# testing.net
KiCad netlist of a schematic drawn in EAGLE
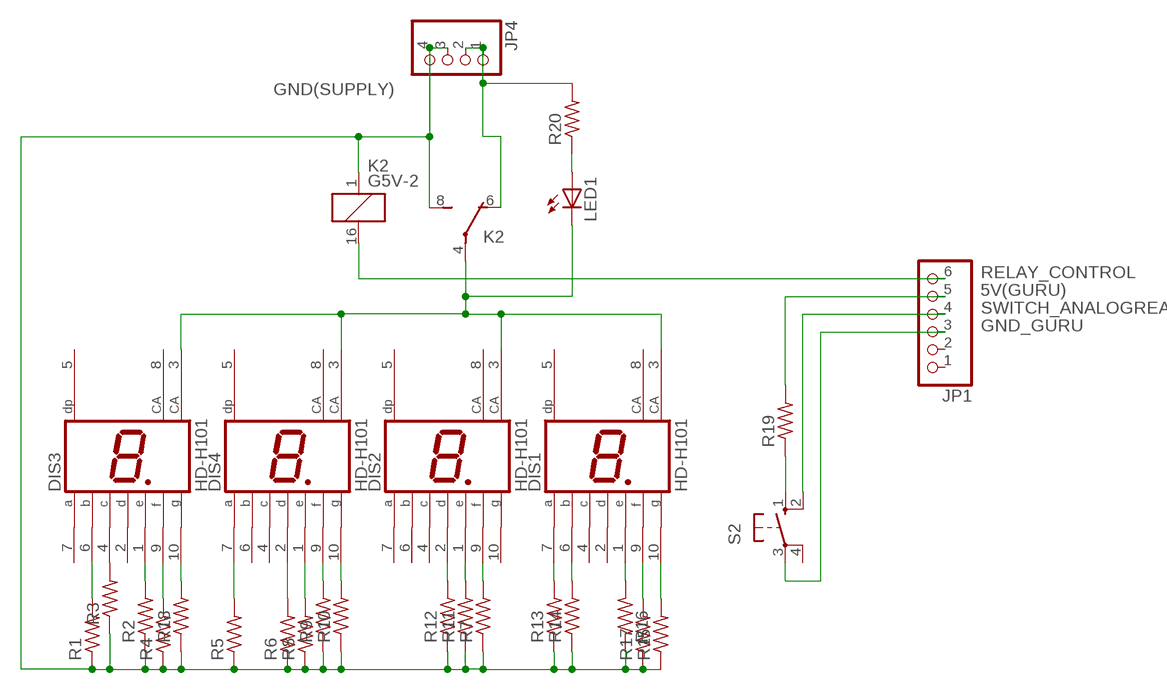
[diagram p0: schematic, sheet 1]

(export (version "E")
  (design (tool "Eeschema 10.0.6"))
  (components
    (comp (ref "DIS1")
      (value "HD-H101")
      (footprint "eagle-import:HDSP-M")
      (libsource (lib "eagle-import") (part "HD-H101"))
    )
    (comp (ref "DIS2")
      (value "HD-H101")
      (footprint "eagle-import:HDSP-M")
      (libsource (lib "eagle-import") (part "HD-H101"))
    )
    (comp (ref "DIS3")
      (value "HD-H101")
      (footprint "eagle-import:HDSP-M")
      (libsource (lib "eagle-import") (part "HD-H101"))
    )
    (comp (ref "DIS4")
      (value "HD-H101")
      (footprint "eagle-import:HDSP-M")
      (libsource (lib "eagle-import") (part "HD-H101"))
    )
    (comp (ref "JP1")
      (value "PINHD-1X6/90")
      (footprint "eagle-import:1X06_90")
      (libsource (lib "eagle-import") (part "PINHD-1X6/90"))
    )
    (comp (ref "JP4")
      (value "PINHD-1X4")
      (footprint "eagle-import:1X04")
      (libsource (lib "eagle-import") (part "PINHD-1X4"))
    )
    (comp (ref "K2")
      (value "G5V-2")
      (footprint "eagle-import:G5V-2")
      (fields (field (name "MPN") "G5V-2 5DC"))
      (libsource (lib "eagle-import") (part "G5V-2"))
    )
    (comp (ref "LED1")
      (value "LED5MM")
      (footprint "eagle-import:LED5MM")
      (libsource (lib "eagle-import") (part "LED5MM"))
    )
    (comp (ref "R1")
      (value "RESISTOR0207/10")
      (footprint "eagle-import:0207_10")
      (libsource (lib "eagle-import") (part "RESISTOR0207/10"))
    )
    (comp (ref "R2")
      (value "RESISTOR0207/10")
      (footprint "eagle-import:0207_10")
      (libsource (lib "eagle-import") (part "RESISTOR0207/10"))
    )
    (comp (ref "R3")
      (value "RESISTOR0207/10")
      (footprint "eagle-import:0207_10")
      (libsource (lib "eagle-import") (part "RESISTOR0207/10"))
    )
    (comp (ref "R4")
      (value "RESISTOR0207/10")
      (footprint "eagle-import:0207_10")
      (libsource (lib "eagle-import") (part "RESISTOR0207/10"))
    )
    (comp (ref "R5")
      (value "RESISTOR0207/10")
      (footprint "eagle-import:0207_10")
      (libsource (lib "eagle-import") (part "RESISTOR0207/10"))
    )
    (comp (ref "R6")
      (value "RESISTOR0207/10")
      (footprint "eagle-import:0207_10")
      (libsource (lib "eagle-import") (part "RESISTOR0207/10"))
    )
    (comp (ref "R7")
      (value "RESISTOR0207/10")
      (footprint "eagle-import:0207_10")
      (libsource (lib "eagle-import") (part "RESISTOR0207/10"))
    )
    (comp (ref "R8")
      (value "RESISTOR0207/10")
      (footprint "eagle-import:0207_10")
      (libsource (lib "eagle-import") (part "RESISTOR0207/10"))
    )
    (comp (ref "R9")
      (value "RESISTOR0207/10")
      (footprint "eagle-import:0207_10")
      (libsource (lib "eagle-import") (part "RESISTOR0207/10"))
    )
    (comp (ref "R10")
      (value "RESISTOR0207/10")
      (footprint "eagle-import:0207_10")
      (libsource (lib "eagle-import") (part "RESISTOR0207/10"))
    )
    (comp (ref "R11")
      (value "RESISTOR0207/10")
      (footprint "eagle-import:0207_10")
      (libsource (lib "eagle-import") (part "RESISTOR0207/10"))
    )
    (comp (ref "R12")
      (value "RESISTOR0207/10")
      (footprint "eagle-import:0207_10")
      (libsource (lib "eagle-import") (part "RESISTOR0207/10"))
    )
    (comp (ref "R13")
      (value "RESISTOR0207/10")
      (footprint "eagle-import:0207_10")
      (libsource (lib "eagle-import") (part "RESISTOR0207/10"))
    )
    (comp (ref "R14")
      (value "RESISTOR0207/10")
      (footprint "eagle-import:0207_10")
      (libsource (lib "eagle-import") (part "RESISTOR0207/10"))
    )
    (comp (ref "R15")
      (value "RESISTOR0207/10")
      (footprint "eagle-import:0207_10")
      (libsource (lib "eagle-import") (part "RESISTOR0207/10"))
    )
    (comp (ref "R16")
      (value "RESISTOR0207/10")
      (footprint "eagle-import:0207_10")
      (libsource (lib "eagle-import") (part "RESISTOR0207/10"))
    )
    (comp (ref "R17")
      (value "RESISTOR0207/10")
      (footprint "eagle-import:0207_10")
      (libsource (lib "eagle-import") (part "RESISTOR0207/10"))
    )
    (comp (ref "R18")
      (value "RESISTOR0207/10")
      (footprint "eagle-import:0207_10")
      (libsource (lib "eagle-import") (part "RESISTOR0207/10"))
    )
    (comp (ref "R19")
      (value "RESISTOR0207/10")
      (footprint "eagle-import:0207_10")
      (libsource (lib "eagle-import") (part "RESISTOR0207/10"))
    )
    (comp (ref "R20")
      (value "RESISTOR0207/10")
      (footprint "eagle-import:0207_10")
      (libsource (lib "eagle-import") (part "RESISTOR0207/10"))
    )
    (comp (ref "S2")
      (value "10-XX")
      (footprint "eagle-import:B3F-10XX")
      (libsource (lib "eagle-import") (part "10-XX"))
    )
  )
  (nets
    (net (code "1") (name "/5V(GURU)") (class "Default")
      (node (ref "JP1") (pin "5") (pinfunction "5_5") (pintype "passive"))
      (node (ref "R19") (pin "2") (pinfunction "2_2") (pintype "passive"))
    )
    (net (code "2") (name "/GND(SUPPLY)") (class "Default")
      (node (ref "JP4") (pin "3") (pinfunction "3_3") (pintype "passive"))
      (node (ref "JP4") (pin "4") (pinfunction "4_4") (pintype "passive"))
      (node (ref "K2") (pin "1") (pinfunction "1_1") (pintype "passive"))
      (node (ref "K2") (pin "8") (pinfunction "S_8") (pintype "passive"))
      (node (ref "R1") (pin "1") (pinfunction "1_1") (pintype "passive"))
      (node (ref "R10") (pin "1") (pinfunction "1_1") (pintype "passive"))
      (node (ref "R11") (pin "1") (pinfunction "1_1") (pintype "passive"))
      (node (ref "R12") (pin "1") (pinfunction "1_1") (pintype "passive"))
      (node (ref "R13") (pin "1") (pinfunction "1_1") (pintype "passive"))
      (node (ref "R14") (pin "1") (pinfunction "1_1") (pintype "passive"))
      (node (ref "R15") (pin "1") (pinfunction "1_1") (pintype "passive"))
      (node (ref "R16") (pin "1") (pinfunction "1_1") (pintype "passive"))
      (node (ref "R17") (pin "1") (pinfunction "1_1") (pintype "passive"))
      (node (ref "R18") (pin "1") (pinfunction "1_1") (pintype "passive"))
      (node (ref "R2") (pin "1") (pinfunction "1_1") (pintype "passive"))
      (node (ref "R3") (pin "1") (pinfunction "1_1") (pintype "passive"))
      (node (ref "R4") (pin "1") (pinfunction "1_1") (pintype "passive"))
      (node (ref "R5") (pin "1") (pinfunction "1_1") (pintype "passive"))
      (node (ref "R6") (pin "1") (pinfunction "1_1") (pintype "passive"))
      (node (ref "R7") (pin "1") (pinfunction "1_1") (pintype "passive"))
      (node (ref "R8") (pin "1") (pinfunction "1_1") (pintype "passive"))
      (node (ref "R9") (pin "1") (pinfunction "1_1") (pintype "passive"))
    )
    (net (code "3") (name "/GND_GURU") (class "Default")
      (node (ref "JP1") (pin "3") (pinfunction "3_3") (pintype "passive"))
      (node (ref "S2") (pin "3") (pinfunction "P_3") (pintype "passive"))
    )
    (net (code "4") (name "/RELAY_CONTROL") (class "Default")
      (node (ref "JP1") (pin "6") (pinfunction "6_6") (pintype "passive"))
      (node (ref "K2") (pin "16") (pinfunction "2_16") (pintype "passive"))
    )
    (net (code "5") (name "/SWITCH_ANALOGREAD") (class "Default")
      (node (ref "JP1") (pin "4") (pinfunction "4_4") (pintype "passive"))
      (node (ref "S2") (pin "2") (pinfunction "S1_2") (pintype "passive"))
    )
    (net (code "6") (name "Net-(DIS1-A)") (class "Default")
      (node (ref "DIS1") (pin "7") (pinfunction "A_7") (pintype "passive"))
      (node (ref "R13") (pin "2") (pinfunction "2_2") (pintype "passive"))
    )
    (net (code "7") (name "Net-(DIS1-B)") (class "Default")
      (node (ref "DIS1") (pin "6") (pinfunction "B_6") (pintype "passive"))
      (node (ref "R14") (pin "2") (pinfunction "2_2") (pintype "passive"))
    )
    (net (code "8") (name "Net-(DIS1-E)") (class "Default")
      (node (ref "DIS1") (pin "1") (pinfunction "E_1") (pintype "passive"))
      (node (ref "R16") (pin "2") (pinfunction "2_2") (pintype "passive"))
    )
    (net (code "9") (name "Net-(DIS1-F)") (class "Default")
      (node (ref "DIS1") (pin "9") (pinfunction "F_9") (pintype "passive"))
      (node (ref "R17") (pin "2") (pinfunction "2_2") (pintype "passive"))
    )
    (net (code "10") (name "Net-(DIS1-G)") (class "Default")
      (node (ref "DIS1") (pin "10") (pinfunction "G_10") (pintype "passive"))
      (node (ref "R15") (pin "2") (pinfunction "2_2") (pintype "passive"))
    )
    (net (code "11") (name "Net-(DIS2-D)") (class "Default")
      (node (ref "DIS2") (pin "2") (pinfunction "D_2") (pintype "passive"))
      (node (ref "R12") (pin "2") (pinfunction "2_2") (pintype "passive"))
    )
    (net (code "12") (name "Net-(DIS2-E)") (class "Default")
      (node (ref "DIS2") (pin "1") (pinfunction "E_1") (pintype "passive"))
      (node (ref "R11") (pin "2") (pinfunction "2_2") (pintype "passive"))
    )
    (net (code "13") (name "Net-(DIS2-F)") (class "Default")
      (node (ref "DIS2") (pin "9") (pinfunction "F_9") (pintype "passive"))
      (node (ref "R7") (pin "2") (pinfunction "2_2") (pintype "passive"))
    )
    (net (code "14") (name "Net-(DIS3-B)") (class "Default")
      (node (ref "DIS3") (pin "6") (pinfunction "B_6") (pintype "passive"))
      (node (ref "R1") (pin "2") (pinfunction "2_2") (pintype "passive"))
    )
    (net (code "15") (name "Net-(DIS3-C)") (class "Default")
      (node (ref "DIS3") (pin "4") (pinfunction "C_4") (pintype "passive"))
      (node (ref "R3") (pin "2") (pinfunction "2_2") (pintype "passive"))
    )
    (net (code "16") (name "Net-(DIS3-E)") (class "Default")
      (node (ref "DIS3") (pin "1") (pinfunction "E_1") (pintype "passive"))
      (node (ref "R2") (pin "2") (pinfunction "2_2") (pintype "passive"))
    )
    (net (code "17") (name "Net-(DIS3-F)") (class "Default")
      (node (ref "DIS3") (pin "9") (pinfunction "F_9") (pintype "passive"))
      (node (ref "R4") (pin "2") (pinfunction "2_2") (pintype "passive"))
    )
    (net (code "18") (name "Net-(DIS3-G)") (class "Default")
      (node (ref "DIS3") (pin "10") (pinfunction "G_10") (pintype "passive"))
      (node (ref "R18") (pin "2") (pinfunction "2_2") (pintype "passive"))
    )
    (net (code "19") (name "Net-(DIS4-A)") (class "Default")
      (node (ref "DIS4") (pin "7") (pinfunction "A_7") (pintype "passive"))
      (node (ref "R5") (pin "2") (pinfunction "2_2") (pintype "passive"))
    )
    (net (code "20") (name "Net-(DIS4-D)") (class "Default")
      (node (ref "DIS4") (pin "2") (pinfunction "D_2") (pintype "passive"))
      (node (ref "R6") (pin "2") (pinfunction "2_2") (pintype "passive"))
    )
    (net (code "21") (name "Net-(DIS4-E)") (class "Default")
      (node (ref "DIS4") (pin "1") (pinfunction "E_1") (pintype "passive"))
      (node (ref "R8") (pin "2") (pinfunction "2_2") (pintype "passive"))
    )
    (net (code "22") (name "Net-(DIS4-F)") (class "Default")
      (node (ref "DIS4") (pin "9") (pinfunction "F_9") (pintype "passive"))
      (node (ref "R9") (pin "2") (pinfunction "2_2") (pintype "passive"))
    )
    (net (code "23") (name "Net-(DIS4-G)") (class "Default")
      (node (ref "DIS4") (pin "10") (pinfunction "G_10") (pintype "passive"))
      (node (ref "R10") (pin "2") (pinfunction "2_2") (pintype "passive"))
    )
    (net (code "24") (name "Net-(K2A-O)") (class "Default")
      (node (ref "JP4") (pin "1") (pinfunction "1_1") (pintype "passive"))
      (node (ref "JP4") (pin "2") (pinfunction "2_2") (pintype "passive"))
      (node (ref "K2") (pin "6") (pinfunction "O_6") (pintype "passive"))
      (node (ref "R20") (pin "2") (pinfunction "2_2") (pintype "passive"))
    )
    (net (code "25") (name "Net-(K2A-P)") (class "Default")
      (node (ref "DIS1") (pin "3") (pinfunction "CA_3") (pintype "passive"))
      (node (ref "DIS2") (pin "3") (pinfunction "CA_3") (pintype "passive"))
      (node (ref "DIS3") (pin "3") (pinfunction "CA_3") (pintype "passive"))
      (node (ref "DIS4") (pin "3") (pinfunction "CA_3") (pintype "passive"))
      (node (ref "K2") (pin "4") (pinfunction "P_4") (pintype "passive"))
      (node (ref "LED1") (pin "K") (pinfunction "C_K") (pintype "passive"))
    )
    (net (code "26") (name "Net-(LED1-PadA)") (class "Default")
      (node (ref "LED1") (pin "A") (pinfunction "A_A") (pintype "passive"))
      (node (ref "R20") (pin "1") (pinfunction "1_1") (pintype "passive"))
    )
    (net (code "27") (name "Net-(S2-S)") (class "Default")
      (node (ref "R19") (pin "1") (pinfunction "1_1") (pintype "passive"))
      (node (ref "S2") (pin "1") (pinfunction "S_1") (pintype "passive"))
    )
    (net (code "28") (name "unconnected-(DIS1-C-Pad4)") (class "Default")
      (node (ref "DIS1") (pin "4") (pinfunction "C_4") (pintype "passive"))
    )
    (net (code "29") (name "unconnected-(DIS1-CA-Pad8)") (class "Default")
      (node (ref "DIS1") (pin "8") (pinfunction "CA_8") (pintype "passive"))
    )
    (net (code "30") (name "unconnected-(DIS1-D-Pad2)") (class "Default")
      (node (ref "DIS1") (pin "2") (pinfunction "D_2") (pintype "passive"))
    )
    (net (code "31") (name "unconnected-(DIS1-DP-Pad5)") (class "Default")
      (node (ref "DIS1") (pin "5") (pinfunction "DP_5") (pintype "passive"))
    )
    (net (code "32") (name "unconnected-(DIS2-A-Pad7)") (class "Default")
      (node (ref "DIS2") (pin "7") (pinfunction "A_7") (pintype "passive"))
    )
    (net (code "33") (name "unconnected-(DIS2-B-Pad6)") (class "Default")
      (node (ref "DIS2") (pin "6") (pinfunction "B_6") (pintype "passive"))
    )
    (net (code "34") (name "unconnected-(DIS2-C-Pad4)") (class "Default")
      (node (ref "DIS2") (pin "4") (pinfunction "C_4") (pintype "passive"))
    )
    (net (code "35") (name "unconnected-(DIS2-CA-Pad8)") (class "Default")
      (node (ref "DIS2") (pin "8") (pinfunction "CA_8") (pintype "passive"))
    )
    (net (code "36") (name "unconnected-(DIS2-DP-Pad5)") (class "Default")
      (node (ref "DIS2") (pin "5") (pinfunction "DP_5") (pintype "passive"))
    )
    (net (code "37") (name "unconnected-(DIS2-G-Pad10)") (class "Default")
      (node (ref "DIS2") (pin "10") (pinfunction "G_10") (pintype "passive"))
    )
    (net (code "38") (name "unconnected-(DIS3-A-Pad7)") (class "Default")
      (node (ref "DIS3") (pin "7") (pinfunction "A_7") (pintype "passive"))
    )
    (net (code "39") (name "unconnected-(DIS3-CA-Pad8)") (class "Default")
      (node (ref "DIS3") (pin "8") (pinfunction "CA_8") (pintype "passive"))
    )
    (net (code "40") (name "unconnected-(DIS3-D-Pad2)") (class "Default")
      (node (ref "DIS3") (pin "2") (pinfunction "D_2") (pintype "passive"))
    )
    (net (code "41") (name "unconnected-(DIS3-DP-Pad5)") (class "Default")
      (node (ref "DIS3") (pin "5") (pinfunction "DP_5") (pintype "passive"))
    )
    (net (code "42") (name "unconnected-(DIS4-B-Pad6)") (class "Default")
      (node (ref "DIS4") (pin "6") (pinfunction "B_6") (pintype "passive"))
    )
    (net (code "43") (name "unconnected-(DIS4-C-Pad4)") (class "Default")
      (node (ref "DIS4") (pin "4") (pinfunction "C_4") (pintype "passive"))
    )
    (net (code "44") (name "unconnected-(DIS4-CA-Pad8)") (class "Default")
      (node (ref "DIS4") (pin "8") (pinfunction "CA_8") (pintype "passive"))
    )
    (net (code "45") (name "unconnected-(DIS4-DP-Pad5)") (class "Default")
      (node (ref "DIS4") (pin "5") (pinfunction "DP_5") (pintype "passive"))
    )
    (net (code "46") (name "unconnected-(JP1-Pad1)") (class "Default")
      (node (ref "JP1") (pin "1") (pinfunction "1_1") (pintype "passive"))
    )
    (net (code "47") (name "unconnected-(JP1-Pad2)") (class "Default")
      (node (ref "JP1") (pin "2") (pinfunction "2_2") (pintype "passive"))
    )
    (net (code "48") (name "unconnected-(S2-P1-Pad4)") (class "Default")
      (node (ref "S2") (pin "4") (pinfunction "P1_4") (pintype "passive"))
    )
  )
)
